# BioPrinter_Schematics.net
KiCad netlist of a schematic drawn in Altium Designer
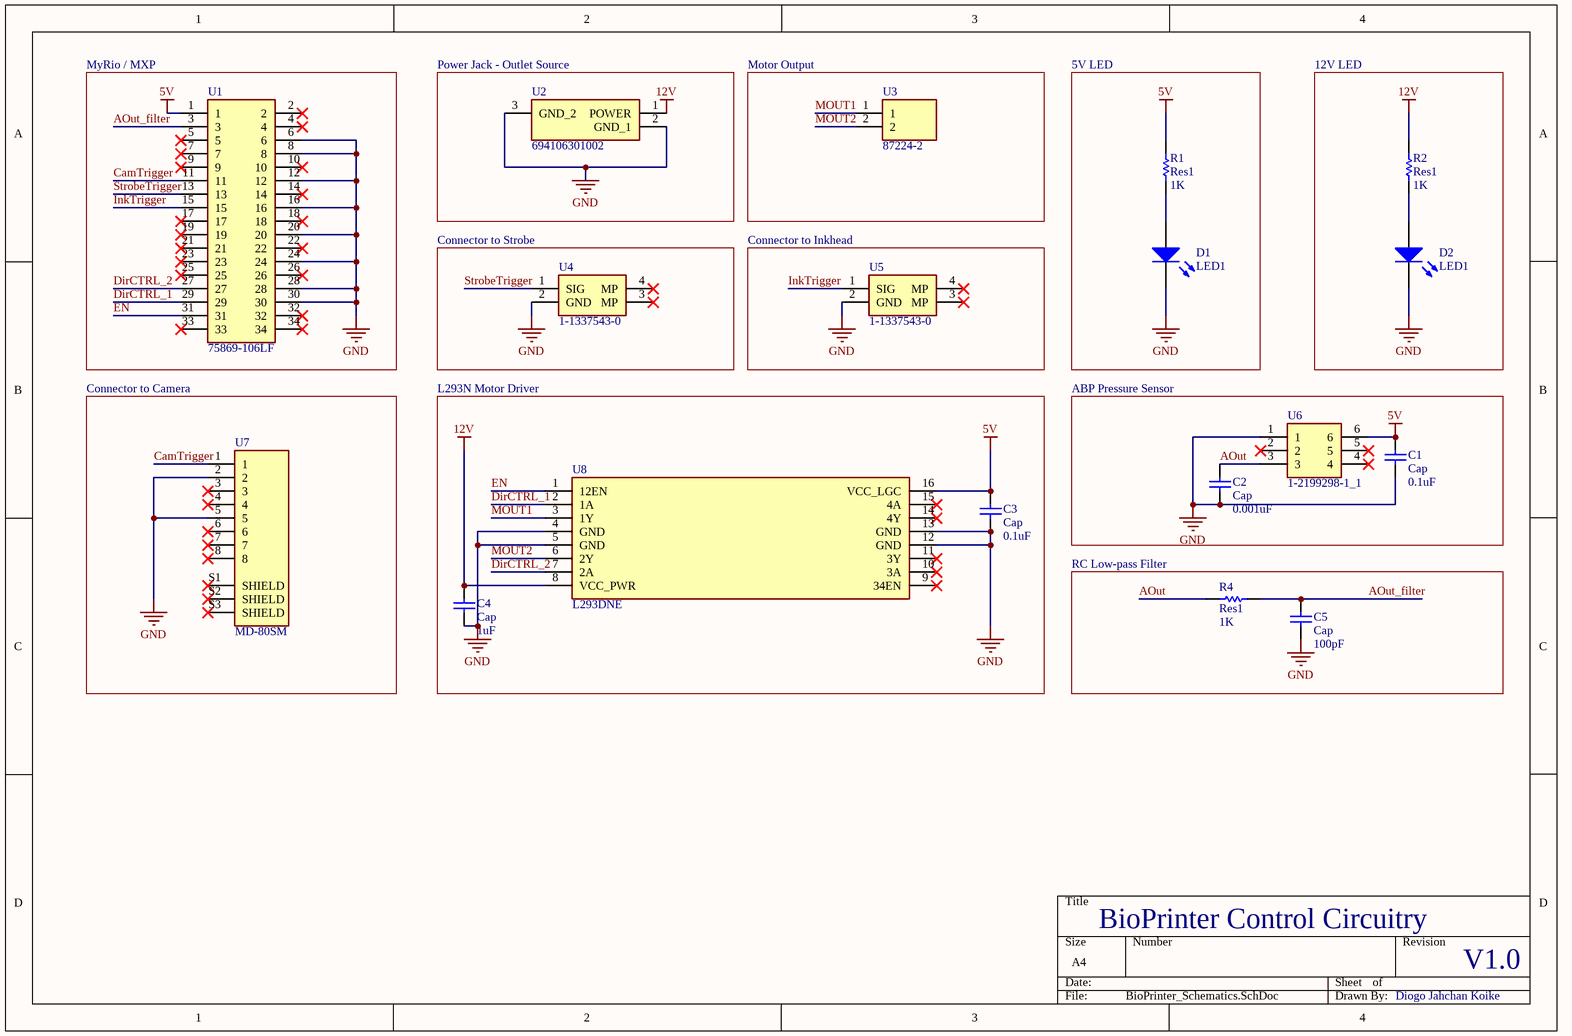
[diagram p0: BioPrinter_Schematics.SchDoc]

(export (version "E")
  (design (tool "Eeschema 10.0.6"))
  (components
    (comp (ref "C1")
      (value "Cap")
      (footprint "RAD-0.3")
      (description "Capacitor")
      (fields (field (name "ALTIUM_VALUE") "0.1uF") (field (name "PUBLISHER") "Altium Limited"))
      (libsource (lib "BioPrinter_Schematics") (part "Cap"))
    )
    (comp (ref "C2")
      (value "Cap")
      (footprint "RAD-0.3")
      (description "Capacitor")
      (fields (field (name "ALTIUM_VALUE") "0.001uF") (field (name "PUBLISHER") "Altium Limited"))
      (libsource (lib "BioPrinter_Schematics") (part "Cap"))
    )
    (comp (ref "C3")
      (value "Cap")
      (footprint "RAD-0.3")
      (description "Capacitor")
      (fields (field (name "ALTIUM_VALUE") "0.1uF") (field (name "PUBLISHER") "Altium Limited"))
      (libsource (lib "BioPrinter_Schematics") (part "Cap"))
    )
    (comp (ref "C4")
      (value "Cap")
      (footprint "RAD-0.3")
      (description "Capacitor")
      (fields (field (name "ALTIUM_VALUE") "1uF") (field (name "PUBLISHER") "Altium Limited"))
      (libsource (lib "BioPrinter_Schematics") (part "Cap"))
    )
    (comp (ref "C5")
      (value "Cap")
      (footprint "RAD-0.3")
      (description "Capacitor")
      (fields (field (name "ALTIUM_VALUE") "100pF") (field (name "PUBLISHER") "Altium Limited"))
      (libsource (lib "BioPrinter_Schematics") (part "Cap"))
    )
    (comp (ref "D1")
      (value "LED1")
      (footprint "LED-1")
      (description "Typical RED GaAs LED")
      (fields (field (name "PUBLISHER") "Altium Limited"))
      (libsource (lib "BioPrinter_Schematics") (part "LED1"))
    )
    (comp (ref "D2")
      (value "LED1")
      (footprint "LED-1")
      (description "Typical RED GaAs LED")
      (fields (field (name "PUBLISHER") "Altium Limited"))
      (libsource (lib "BioPrinter_Schematics") (part "LED1"))
    )
    (comp (ref "R1")
      (value "Res1")
      (footprint "AXIAL-0.3")
      (description "Resistor")
      (fields (field (name "ALTIUM_VALUE") "1K") (field (name "PUBLISHER") "Altium Limited"))
      (libsource (lib "BioPrinter_Schematics") (part "Res1"))
    )
    (comp (ref "R2")
      (value "Res1")
      (footprint "AXIAL-0.3")
      (description "Resistor")
      (fields (field (name "ALTIUM_VALUE") "1K") (field (name "PUBLISHER") "Altium Limited"))
      (libsource (lib "BioPrinter_Schematics") (part "Res1"))
    )
    (comp (ref "R4")
      (value "Res1")
      (footprint "AXIAL-0.3")
      (description "Resistor")
      (fields (field (name "ALTIUM_VALUE") "1K") (field (name "PUBLISHER") "Altium Limited"))
      (libsource (lib "BioPrinter_Schematics") (part "Res1"))
    )
    (comp (ref "U1")
      (value "75869-106LF")
      (footprint "SHDR34W62P254_2X17_5039X920X957P")
      (description "Connector")
      (fields (field (name "MOUSER PART NUMBER") "649-75869-106LF"))
      (libsource (lib "BioPrinter_Schematics") (part "75869-106LF"))
    )
    (comp (ref "U2")
      (value "694106301002")
      (footprint "694106301002_1")
      (description "WURTH ELEKTRONIK - 694106301002 - CONNECTOR, POWER ENTRY, JACK, 3A, 20VDC")
      (fields (field (name "MOUSER PART NUMBER") "710-694106301002"))
      (libsource (lib "BioPrinter_Schematics") (part "694106301002"))
    )
    (comp (ref "U3")
      (value "87224-2")
      (footprint "872242")
      (description "Connector")
      (fields (field (name "MOUSER PART NUMBER") "571-872242"))
      (libsource (lib "BioPrinter_Schematics") (part "87224-2"))
    )
    (comp (ref "U4")
      (value "1-1337543-0")
      (footprint "1-1337543-0")
      (description "BNC Ins R/A PCB Skt 50Ohm White")
      (fields (field (name "MOUSER PART NUMBER") "571-1-1337543-0"))
      (libsource (lib "BioPrinter_Schematics") (part "1-1337543-0"))
    )
    (comp (ref "U5")
      (value "1-1337543-0")
      (footprint "1-1337543-0")
      (description "BNC Ins R/A PCB Skt 50Ohm White")
      (fields (field (name "MOUSER PART NUMBER") "571-1-1337543-0"))
      (libsource (lib "BioPrinter_Schematics") (part "1-1337543-0"))
    )
    (comp (ref "U6")
      (value "1-2199298-1_1")
      (footprint "DIPS762W70P254L762H510Q6N - duplicate")
      (description "Connector")
      (fields
        (field (name "MANUFACTURER_PART_NUMBER") "1-2199298-1")
        (field (name "MOUSER PART NUMBER") "571-1-2199298-1")
      )
      (libsource (lib "BioPrinter_Schematics") (part "1-2199298-1_1"))
    )
    (comp (ref "U7")
      (value "MD-80SM")
      (footprint "CUI_MD-80SM")
      (fields (field (name "MF") "{'manufacturer': u'CUI'}"))
      (libsource (lib "BioPrinter_Schematics") (part "MD-80SM"))
    )
    (comp (ref "U8")
      (value "L293DNE")
      (footprint "DIP762W53P254L1980H508Q16N")
      (description "Integrated Circuit")
      (fields (field (name "MOUSER PART NUMBER") "595-L293DNE"))
      (libsource (lib "BioPrinter_Schematics") (part "L293DNE"))
    )
  )
  (nets
    (net (code "1") (name "/AOut") (class "Default")
      (node (ref "C2") (pin "2") (pinfunction "2_2") (pintype "passive"))
      (node (ref "R4") (pin "1") (pinfunction "1_1") (pintype "passive"))
      (node (ref "U6") (pin "3") (pinfunction "3_3") (pintype "passive"))
    )
    (net (code "2") (name "/AOut_filter") (class "Default")
      (node (ref "C5") (pin "2") (pinfunction "2_2") (pintype "passive"))
      (node (ref "R4") (pin "2") (pinfunction "2_2") (pintype "passive"))
      (node (ref "U1") (pin "3") (pinfunction "3_3") (pintype "passive"))
    )
    (net (code "3") (name "/CamTrigger") (class "Default")
      (node (ref "U1") (pin "11") (pinfunction "11_11") (pintype "passive"))
      (node (ref "U7") (pin "1") (pinfunction "1_1") (pintype "passive"))
    )
    (net (code "4") (name "/DirCTRL_1") (class "Default")
      (node (ref "U1") (pin "29") (pinfunction "29_29") (pintype "passive"))
      (node (ref "U8") (pin "2") (pinfunction "1A_2") (pintype "passive"))
    )
    (net (code "5") (name "/DirCTRL_2") (class "Default")
      (node (ref "U1") (pin "27") (pinfunction "27_27") (pintype "passive"))
      (node (ref "U8") (pin "7") (pinfunction "2A_7") (pintype "passive"))
    )
    (net (code "6") (name "/EN") (class "Default")
      (node (ref "U1") (pin "31") (pinfunction "31_31") (pintype "passive"))
      (node (ref "U8") (pin "1") (pinfunction "12EN_1") (pintype "passive"))
    )
    (net (code "7") (name "/InkTrigger") (class "Default")
      (node (ref "U1") (pin "15") (pinfunction "15_15") (pintype "passive"))
      (node (ref "U5") (pin "1") (pinfunction "SIG_1") (pintype "passive"))
    )
    (net (code "8") (name "/MOUT1") (class "Default")
      (node (ref "U3") (pin "1") (pinfunction "1_1") (pintype "passive"))
      (node (ref "U8") (pin "3") (pinfunction "1Y_3") (pintype "passive"))
    )
    (net (code "9") (name "/MOUT2") (class "Default")
      (node (ref "U3") (pin "2") (pinfunction "2_2") (pintype "passive"))
      (node (ref "U8") (pin "6") (pinfunction "2Y_6") (pintype "passive"))
    )
    (net (code "10") (name "/StrobeTrigger") (class "Default")
      (node (ref "U1") (pin "13") (pinfunction "13_13") (pintype "passive"))
      (node (ref "U4") (pin "1") (pinfunction "SIG_1") (pintype "passive"))
    )
    (net (code "11") (name "5V") (class "Default")
      (node (ref "C1") (pin "2") (pinfunction "2_2") (pintype "passive"))
      (node (ref "C3") (pin "2") (pinfunction "2_2") (pintype "passive"))
      (node (ref "R1") (pin "2") (pinfunction "2_2") (pintype "passive"))
      (node (ref "U1") (pin "1") (pinfunction "1_1") (pintype "passive"))
      (node (ref "U6") (pin "6") (pinfunction "6_6") (pintype "passive"))
      (node (ref "U8") (pin "16") (pinfunction "VCC_LGC_16") (pintype "passive"))
    )
    (net (code "12") (name "12V") (class "Default")
      (node (ref "C4") (pin "2") (pinfunction "2_2") (pintype "passive"))
      (node (ref "R2") (pin "2") (pinfunction "2_2") (pintype "passive"))
      (node (ref "U2") (pin "1") (pinfunction "POWER_1") (pintype "passive"))
      (node (ref "U8") (pin "8") (pinfunction "VCC_PWR_8") (pintype "passive"))
    )
    (net (code "13") (name "GND") (class "Default")
      (node (ref "C1") (pin "1") (pinfunction "1_1") (pintype "passive"))
      (node (ref "C2") (pin "1") (pinfunction "1_1") (pintype "passive"))
      (node (ref "C3") (pin "1") (pinfunction "1_1") (pintype "passive"))
      (node (ref "C4") (pin "1") (pinfunction "1_1") (pintype "passive"))
      (node (ref "C5") (pin "1") (pinfunction "1_1") (pintype "passive"))
      (node (ref "D1") (pin "2") (pinfunction "K_2") (pintype "passive"))
      (node (ref "D2") (pin "2") (pinfunction "K_2") (pintype "passive"))
      (node (ref "U1") (pin "12") (pinfunction "12_12") (pintype "passive"))
      (node (ref "U1") (pin "16") (pinfunction "16_16") (pintype "passive"))
      (node (ref "U1") (pin "20") (pinfunction "20_20") (pintype "passive"))
      (node (ref "U1") (pin "24") (pinfunction "24_24") (pintype "passive"))
      (node (ref "U1") (pin "28") (pinfunction "28_28") (pintype "passive"))
      (node (ref "U1") (pin "30") (pinfunction "30_30") (pintype "passive"))
      (node (ref "U1") (pin "6") (pinfunction "6_6") (pintype "passive"))
      (node (ref "U1") (pin "8") (pinfunction "8_8") (pintype "passive"))
      (node (ref "U2") (pin "2") (pinfunction "GND_1_2") (pintype "passive"))
      (node (ref "U2") (pin "3") (pinfunction "GND_2_3") (pintype "passive"))
      (node (ref "U4") (pin "2") (pinfunction "GND_2") (pintype "passive"))
      (node (ref "U5") (pin "2") (pinfunction "GND_2") (pintype "passive"))
      (node (ref "U6") (pin "1") (pinfunction "1_1") (pintype "passive"))
      (node (ref "U7") (pin "2") (pinfunction "2_2") (pintype "passive"))
      (node (ref "U7") (pin "5") (pinfunction "5_5") (pintype "passive"))
      (node (ref "U8") (pin "12") (pinfunction "GND_12") (pintype "passive"))
      (node (ref "U8") (pin "13") (pinfunction "GND_13") (pintype "passive"))
      (node (ref "U8") (pin "4") (pinfunction "GND_4") (pintype "passive"))
      (node (ref "U8") (pin "5") (pinfunction "GND_5") (pintype "passive"))
    )
    (net (code "14") (name "Net-(D1-A)") (class "Default")
      (node (ref "D1") (pin "1") (pinfunction "A_1") (pintype "passive"))
      (node (ref "R1") (pin "1") (pinfunction "1_1") (pintype "passive"))
    )
    (net (code "15") (name "Net-(D2-A)") (class "Default")
      (node (ref "D2") (pin "1") (pinfunction "A_1") (pintype "passive"))
      (node (ref "R2") (pin "1") (pinfunction "1_1") (pintype "passive"))
    )
    (net (code "16") (name "unconnected-(U1-Pad2)") (class "Default")
      (node (ref "U1") (pin "2") (pinfunction "2_2") (pintype "passive+no_connect"))
    )
    (net (code "17") (name "unconnected-(U1-Pad4)") (class "Default")
      (node (ref "U1") (pin "4") (pinfunction "4_4") (pintype "passive+no_connect"))
    )
    (net (code "18") (name "unconnected-(U1-Pad5)") (class "Default")
      (node (ref "U1") (pin "5") (pinfunction "5_5") (pintype "passive+no_connect"))
    )
    (net (code "19") (name "unconnected-(U1-Pad7)") (class "Default")
      (node (ref "U1") (pin "7") (pinfunction "7_7") (pintype "passive+no_connect"))
    )
    (net (code "20") (name "unconnected-(U1-Pad9)") (class "Default")
      (node (ref "U1") (pin "9") (pinfunction "9_9") (pintype "passive+no_connect"))
    )
    (net (code "21") (name "unconnected-(U1-Pad10)") (class "Default")
      (node (ref "U1") (pin "10") (pinfunction "10_10") (pintype "passive+no_connect"))
    )
    (net (code "22") (name "unconnected-(U1-Pad14)") (class "Default")
      (node (ref "U1") (pin "14") (pinfunction "14_14") (pintype "passive+no_connect"))
    )
    (net (code "23") (name "unconnected-(U1-Pad17)") (class "Default")
      (node (ref "U1") (pin "17") (pinfunction "17_17") (pintype "passive+no_connect"))
    )
    (net (code "24") (name "unconnected-(U1-Pad18)") (class "Default")
      (node (ref "U1") (pin "18") (pinfunction "18_18") (pintype "passive+no_connect"))
    )
    (net (code "25") (name "unconnected-(U1-Pad19)") (class "Default")
      (node (ref "U1") (pin "19") (pinfunction "19_19") (pintype "passive+no_connect"))
    )
    (net (code "26") (name "unconnected-(U1-Pad21)") (class "Default")
      (node (ref "U1") (pin "21") (pinfunction "21_21") (pintype "passive+no_connect"))
    )
    (net (code "27") (name "unconnected-(U1-Pad22)") (class "Default")
      (node (ref "U1") (pin "22") (pinfunction "22_22") (pintype "passive+no_connect"))
    )
    (net (code "28") (name "unconnected-(U1-Pad23)") (class "Default")
      (node (ref "U1") (pin "23") (pinfunction "23_23") (pintype "passive+no_connect"))
    )
    (net (code "29") (name "unconnected-(U1-Pad25)") (class "Default")
      (node (ref "U1") (pin "25") (pinfunction "25_25") (pintype "passive+no_connect"))
    )
    (net (code "30") (name "unconnected-(U1-Pad26)") (class "Default")
      (node (ref "U1") (pin "26") (pinfunction "26_26") (pintype "passive+no_connect"))
    )
    (net (code "31") (name "unconnected-(U1-Pad32)") (class "Default")
      (node (ref "U1") (pin "32") (pinfunction "32_32") (pintype "passive+no_connect"))
    )
    (net (code "32") (name "unconnected-(U1-Pad33)") (class "Default")
      (node (ref "U1") (pin "33") (pinfunction "33_33") (pintype "passive+no_connect"))
    )
    (net (code "33") (name "unconnected-(U1-Pad34)") (class "Default")
      (node (ref "U1") (pin "34") (pinfunction "34_34") (pintype "passive+no_connect"))
    )
    (net (code "34") (name "unconnected-(U4-MP-Pad3)") (class "Default")
      (node (ref "U4") (pin "3") (pinfunction "MP_3") (pintype "passive+no_connect"))
    )
    (net (code "35") (name "unconnected-(U4-MP-Pad4)") (class "Default")
      (node (ref "U4") (pin "4") (pinfunction "MP_4") (pintype "passive+no_connect"))
    )
    (net (code "36") (name "unconnected-(U5-MP-Pad3)") (class "Default")
      (node (ref "U5") (pin "3") (pinfunction "MP_3") (pintype "passive+no_connect"))
    )
    (net (code "37") (name "unconnected-(U5-MP-Pad4)") (class "Default")
      (node (ref "U5") (pin "4") (pinfunction "MP_4") (pintype "passive+no_connect"))
    )
    (net (code "38") (name "unconnected-(U6-Pad2)") (class "Default")
      (node (ref "U6") (pin "2") (pinfunction "2_2") (pintype "passive+no_connect"))
    )
    (net (code "39") (name "unconnected-(U6-Pad4)") (class "Default")
      (node (ref "U6") (pin "4") (pinfunction "4_4") (pintype "passive+no_connect"))
    )
    (net (code "40") (name "unconnected-(U6-Pad5)") (class "Default")
      (node (ref "U6") (pin "5") (pinfunction "5_5") (pintype "passive+no_connect"))
    )
    (net (code "41") (name "unconnected-(U7-Pad3)") (class "Default")
      (node (ref "U7") (pin "3") (pinfunction "3_3") (pintype "passive+no_connect"))
    )
    (net (code "42") (name "unconnected-(U7-Pad4)") (class "Default")
      (node (ref "U7") (pin "4") (pinfunction "4_4") (pintype "passive+no_connect"))
    )
    (net (code "43") (name "unconnected-(U7-Pad6)") (class "Default")
      (node (ref "U7") (pin "6") (pinfunction "6_6") (pintype "passive+no_connect"))
    )
    (net (code "44") (name "unconnected-(U7-Pad7)") (class "Default")
      (node (ref "U7") (pin "7") (pinfunction "7_7") (pintype "passive+no_connect"))
    )
    (net (code "45") (name "unconnected-(U7-Pad8)") (class "Default")
      (node (ref "U7") (pin "8") (pinfunction "8_8") (pintype "passive+no_connect"))
    )
    (net (code "46") (name "unconnected-(U7-SHIELD-PadS1)") (class "Default")
      (node (ref "U7") (pin "S1") (pinfunction "SHIELD_S1") (pintype "passive+no_connect"))
    )
    (net (code "47") (name "unconnected-(U7-SHIELD-PadS2)") (class "Default")
      (node (ref "U7") (pin "S2") (pinfunction "SHIELD_S2") (pintype "passive+no_connect"))
    )
    (net (code "48") (name "unconnected-(U7-SHIELD-PadS3)") (class "Default")
      (node (ref "U7") (pin "S3") (pinfunction "SHIELD_S3") (pintype "passive+no_connect"))
    )
    (net (code "49") (name "unconnected-(U8-3A-Pad10)") (class "Default")
      (node (ref "U8") (pin "10") (pinfunction "3A_10") (pintype "passive+no_connect"))
    )
    (net (code "50") (name "unconnected-(U8-3Y-Pad11)") (class "Default")
      (node (ref "U8") (pin "11") (pinfunction "3Y_11") (pintype "passive+no_connect"))
    )
    (net (code "51") (name "unconnected-(U8-4A-Pad15)") (class "Default")
      (node (ref "U8") (pin "15") (pinfunction "4A_15") (pintype "passive+no_connect"))
    )
    (net (code "52") (name "unconnected-(U8-4Y-Pad14)") (class "Default")
      (node (ref "U8") (pin "14") (pinfunction "4Y_14") (pintype "passive+no_connect"))
    )
    (net (code "53") (name "unconnected-(U8-34EN-Pad9)") (class "Default")
      (node (ref "U8") (pin "9") (pinfunction "34EN_9") (pintype "passive+no_connect"))
    )
  )
)
